# Sensors_and_External_Interfaces.net
KiCad netlist of a schematic drawn in Altium Designer
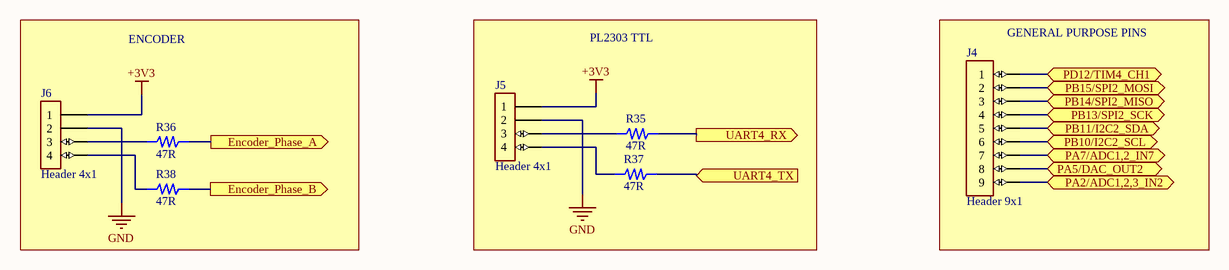
[diagram p0: Sensors_and_External_Interfaces.SchDoc]

(export (version "E")
  (design (tool "Eeschema 10.0.6"))
  (components
    (comp (ref "J4")
      (value "Header 9x1")
      (footprint "9x1 Header")
      (description "PIN HEADER 5PIN (5x1) 2.54mm THT V/T")
      (fields (field (name "MANUFACTURER") "CONNFLY"))
      (libsource (lib "Motor Controller SchLib") (part "Header 9x1"))
    )
    (comp (ref "J5")
      (value "Header 4x1")
      (footprint "4x1 Header")
      (description "PIN HEADER 5PIN (4x1) 2.54mm THT V/T")
      (fields (field (name "MANUFACTURER") "AMPHENOL"))
      (libsource (lib "Motor Controller SchLib") (part "Header 4x1 for Encoder"))
    )
    (comp (ref "J6")
      (value "Header 4x1")
      (footprint "4x1 Header")
      (description "PIN HEADER 5PIN (4x1) 2.54mm THT V/T")
      (fields (field (name "MANUFACTURER") "AMPHENOL"))
      (libsource (lib "Motor Controller SchLib") (part "Header 4x1 for Encoder"))
    )
    (comp (ref "R35")
      (value "47R")
      (footprint "ROYALOHM 0603 RES")
      (description "RES. 0603 47 Ohms 1% 1/8W-S 100PPM")
      (fields (field (name "POWER") "1/8W") (field (name "TOLERANCE") "%1"))
      (libsource (lib "Motor Controller SchLib") (part "RES 0603 47R"))
    )
    (comp (ref "R36")
      (value "47R")
      (footprint "ROYALOHM 0603 RES")
      (description "RES. 0603 47 Ohms 1% 1/8W-S 100PPM")
      (fields (field (name "POWER") "1/8W") (field (name "TOLERANCE") "%1"))
      (libsource (lib "Motor Controller SchLib") (part "RES 0603 47R"))
    )
    (comp (ref "R37")
      (value "47R")
      (footprint "ROYALOHM 0603 RES")
      (description "RES. 0603 47 Ohms 1% 1/8W-S 100PPM")
      (fields (field (name "POWER") "1/8W") (field (name "TOLERANCE") "%1"))
      (libsource (lib "Motor Controller SchLib") (part "RES 0603 47R"))
    )
    (comp (ref "R38")
      (value "47R")
      (footprint "ROYALOHM 0603 RES")
      (description "RES. 0603 47 Ohms 1% 1/8W-S 100PPM")
      (fields (field (name "POWER") "1/8W") (field (name "TOLERANCE") "%1"))
      (libsource (lib "Motor Controller SchLib") (part "RES 0603 47R"))
    )
  )
  (nets
    (net (code "1") (name "+3V3") (class "Default")
      (node (ref "J5") (pin "1") (pinfunction "1_1") (pintype "power_in"))
      (node (ref "J6") (pin "1") (pinfunction "1_1") (pintype "power_in"))
    )
    (net (code "2") (name "/Encoder_Phase_A") (class "Default")
      (node (ref "R36") (pin "2") (pinfunction "2_2") (pintype "passive"))
    )
    (net (code "3") (name "/Encoder_Phase_B") (class "Default")
      (node (ref "R38") (pin "2") (pinfunction "2_2") (pintype "passive"))
    )
    (net (code "4") (name "/PA2{slash}ADC1,2,3_IN2") (class "Default")
      (node (ref "J4") (pin "9") (pinfunction "9_9") (pintype "bidirectional"))
    )
    (net (code "5") (name "/PA5{slash}DAC_OUT2") (class "Default")
      (node (ref "J4") (pin "8") (pinfunction "8_8") (pintype "bidirectional"))
    )
    (net (code "6") (name "/PA7{slash}ADC1,2_IN7") (class "Default")
      (node (ref "J4") (pin "7") (pinfunction "7_7") (pintype "bidirectional"))
    )
    (net (code "7") (name "/PB10{slash}I2C2_SCL") (class "Default")
      (node (ref "J4") (pin "6") (pinfunction "6_6") (pintype "bidirectional"))
    )
    (net (code "8") (name "/PB11{slash}I2C2_SDA") (class "Default")
      (node (ref "J4") (pin "5") (pinfunction "5_5") (pintype "bidirectional"))
    )
    (net (code "9") (name "/PB13{slash}SPI2_SCK") (class "Default")
      (node (ref "J4") (pin "4") (pinfunction "4_4") (pintype "bidirectional"))
    )
    (net (code "10") (name "/PB14{slash}SPI2_MISO") (class "Default")
      (node (ref "J4") (pin "3") (pinfunction "3_3") (pintype "bidirectional"))
    )
    (net (code "11") (name "/PB15{slash}SPI2_MOSI") (class "Default")
      (node (ref "J4") (pin "2") (pinfunction "2_2") (pintype "bidirectional"))
    )
    (net (code "12") (name "/PD12{slash}TIM4_CH1") (class "Default")
      (node (ref "J4") (pin "1") (pinfunction "1_1") (pintype "bidirectional"))
    )
    (net (code "13") (name "/UART4_RX") (class "Default")
      (node (ref "R35") (pin "2") (pinfunction "2_2") (pintype "passive"))
    )
    (net (code "14") (name "/UART4_TX") (class "Default")
      (node (ref "R37") (pin "2") (pinfunction "2_2") (pintype "passive"))
    )
    (net (code "15") (name "GND") (class "Default")
      (node (ref "J5") (pin "2") (pinfunction "2_2") (pintype "passive"))
      (node (ref "J6") (pin "2") (pinfunction "2_2") (pintype "passive"))
    )
    (net (code "16") (name "Net-(J5-Pad3)") (class "Default")
      (node (ref "J5") (pin "3") (pinfunction "3_3") (pintype "bidirectional"))
      (node (ref "R35") (pin "1") (pinfunction "1_1") (pintype "passive"))
    )
    (net (code "17") (name "Net-(J5-Pad4)") (class "Default")
      (node (ref "J5") (pin "4") (pinfunction "4_4") (pintype "bidirectional"))
      (node (ref "R37") (pin "1") (pinfunction "1_1") (pintype "passive"))
    )
    (net (code "18") (name "Net-(J6-Pad3)") (class "Default")
      (node (ref "J6") (pin "3") (pinfunction "3_3") (pintype "bidirectional"))
      (node (ref "R36") (pin "1") (pinfunction "1_1") (pintype "passive"))
    )
    (net (code "19") (name "Net-(J6-Pad4)") (class "Default")
      (node (ref "J6") (pin "4") (pinfunction "4_4") (pintype "bidirectional"))
      (node (ref "R38") (pin "1") (pinfunction "1_1") (pintype "passive"))
    )
  )
)
